# USB-C.net
KiCad netlist of a schematic drawn in Altium Designer
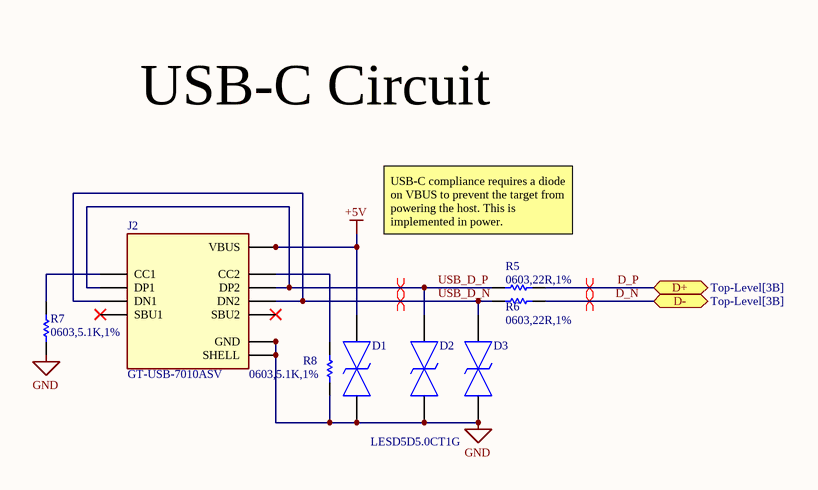
[diagram p0: USB-C.SchDoc]

(export (version "E")
  (design (tool "Eeschema 10.0.6"))
  (components
    (comp (ref "D1")
      (value "LESD5D5.0CT1G")
      (footprint "LESD5D50CT1G")
      (description "9.4A 18.6V 5.6V Bidirectional 5V SOD-523 ESD and Surge Protection (TVS/ESD) ROHS")
      (fields (field (name "LCSC PART NUMBER") "C383211"))
      (libsource (lib "LC-SchLib") (part "LESD5D5.0CT1G"))
    )
    (comp (ref "D2")
      (value "LESD5D5.0CT1G")
      (footprint "LESD5D50CT1G")
      (description "9.4A 18.6V 5.6V Bidirectional 5V SOD-523 ESD and Surge Protection (TVS/ESD) ROHS")
      (fields (field (name "LCSC PART NUMBER") "C383211"))
      (libsource (lib "LC-SchLib") (part "LESD5D5.0CT1G"))
    )
    (comp (ref "D3")
      (value "LESD5D5.0CT1G")
      (footprint "LESD5D50CT1G")
      (description "9.4A 18.6V 5.6V Bidirectional 5V SOD-523 ESD and Surge Protection (TVS/ESD) ROHS")
      (fields (field (name "LCSC PART NUMBER") "C383211"))
      (libsource (lib "LC-SchLib") (part "LESD5D5.0CT1G"))
    )
    (comp (ref "J2")
      (value "GT-USB-7010ASV")
      (footprint "USB-C-SMD_G-SWITCH_GT-USB-7010ASV")
      (description "USB 2.0 3A 1 Surface Mount, Right Angle 16P Female -40℃~+85℃ Type-C SMD USB Connectors ROHS")
      (fields (field (name "LCSC PART NUMBER") "C2988369"))
      (libsource (lib "LC-SchLib") (part "GT-USB-7010ASV"))
    )
    (comp (ref "R5")
      (value "0603,22R,1%")
      (footprint "RESC1608X55N")
      (description "100mW Thick Film Resistor 75V ±100ppm/℃ ±1% 22Ω 0603 Chip Resistor - Surface Mount ROHS")
      (fields
        (field (name "MANUFACTURER_PART_NUMBER") "RC0603FR-0722RL")
        (field (name "MOUSER PART NUMBER") "603-RC0603FR-0722RL")
      )
      (libsource (lib "LC-SchLib") (part "RC0603FR-0722RL"))
    )
    (comp (ref "R6")
      (value "0603,22R,1%")
      (footprint "RESC1608X55N")
      (description "100mW Thick Film Resistor 75V ±100ppm/℃ ±1% 22Ω 0603 Chip Resistor - Surface Mount ROHS")
      (fields
        (field (name "MANUFACTURER_PART_NUMBER") "RC0603FR-0722RL")
        (field (name "MOUSER PART NUMBER") "603-RC0603FR-0722RL")
      )
      (libsource (lib "LC-SchLib") (part "RC0603FR-0722RL"))
    )
    (comp (ref "R7")
      (value "0603,5.1K,1%")
      (footprint "RESC1608X55N")
      (description "100mW Thick Film Resistor 75V ±100ppm/℃ ±1% 5.1kΩ 0603 Chip Resistor - Surface Mount ROHS")
      (fields
        (field (name "MANUFACTURER_PART_NUMBER") "RC0603FR-0710KL")
        (field (name "MOUSER PART NUMBER") "603-RC0603FR-0710KL")
      )
      (libsource (lib "LC-SchLib") (part "RC0603FR-075K1L"))
    )
    (comp (ref "R8")
      (value "0603,5.1K,1%")
      (footprint "RESC1608X55N")
      (description "100mW Thick Film Resistor 75V ±100ppm/℃ ±1% 5.1kΩ 0603 Chip Resistor - Surface Mount ROHS")
      (fields
        (field (name "MANUFACTURER_PART_NUMBER") "RC0603FR-0710KL")
        (field (name "MOUSER PART NUMBER") "603-RC0603FR-0710KL")
      )
      (libsource (lib "LC-SchLib") (part "RC0603FR-075K1L"))
    )
  )
  (nets
    (net (code "1") (name "+5V") (class "Default")
      (node (ref "D1") (pin "2") (pinfunction "2_2") (pintype "passive"))
      (node (ref "J2") (pin "A4B9") (pinfunction "VBUS_A4B9") (pintype "passive"))
      (node (ref "J2") (pin "B4A9") (pinfunction "VBUS_B4A9") (pintype "passive"))
    )
    (net (code "2") (name "/D_N") (class "Default")
      (node (ref "R6") (pin "2") (pinfunction "2_2") (pintype "passive"))
    )
    (net (code "3") (name "/D_P") (class "Default")
      (node (ref "R5") (pin "2") (pinfunction "2_2") (pintype "passive"))
    )
    (net (code "4") (name "/USB_D_N") (class "Default")
      (node (ref "D3") (pin "2") (pinfunction "2_2") (pintype "passive"))
      (node (ref "J2") (pin "A7") (pinfunction "DN1_A7") (pintype "passive"))
      (node (ref "J2") (pin "B7") (pinfunction "DN2_B7") (pintype "passive"))
      (node (ref "R6") (pin "1") (pinfunction "1_1") (pintype "passive"))
    )
    (net (code "5") (name "/USB_D_P") (class "Default")
      (node (ref "D2") (pin "2") (pinfunction "2_2") (pintype "passive"))
      (node (ref "J2") (pin "A6") (pinfunction "DP1_A6") (pintype "passive"))
      (node (ref "J2") (pin "B6") (pinfunction "DP2_B6") (pintype "passive"))
      (node (ref "R5") (pin "1") (pinfunction "1_1") (pintype "passive"))
    )
    (net (code "6") (name "GND") (class "Default")
      (node (ref "D1") (pin "1") (pinfunction "1_1") (pintype "passive"))
      (node (ref "D2") (pin "1") (pinfunction "1_1") (pintype "passive"))
      (node (ref "D3") (pin "1") (pinfunction "1_1") (pintype "passive"))
      (node (ref "J2") (pin "1") (pinfunction "SHELL_1") (pintype "passive"))
      (node (ref "J2") (pin "2") (pinfunction "SHELL_2") (pintype "passive"))
      (node (ref "J2") (pin "3") (pinfunction "SHELL_3") (pintype "passive"))
      (node (ref "J2") (pin "4") (pinfunction "SHELL_4") (pintype "passive"))
      (node (ref "J2") (pin "A1B12") (pinfunction "GND_A1B12") (pintype "passive"))
      (node (ref "J2") (pin "B1A12") (pinfunction "GND_B1A12") (pintype "passive"))
      (node (ref "R7") (pin "1") (pinfunction "1_1") (pintype "passive"))
      (node (ref "R8") (pin "1") (pinfunction "1_1") (pintype "passive"))
    )
    (net (code "7") (name "Net-(J2-CC1)") (class "Default")
      (node (ref "J2") (pin "A5") (pinfunction "CC1_A5") (pintype "passive"))
      (node (ref "R7") (pin "2") (pinfunction "2_2") (pintype "passive"))
    )
    (net (code "8") (name "Net-(J2-CC2)") (class "Default")
      (node (ref "J2") (pin "B5") (pinfunction "CC2_B5") (pintype "passive"))
      (node (ref "R8") (pin "2") (pinfunction "2_2") (pintype "passive"))
    )
    (net (code "9") (name "unconnected-(J2-SBU1-PadA8)") (class "Default")
      (node (ref "J2") (pin "A8") (pinfunction "SBU1_A8") (pintype "passive+no_connect"))
    )
    (net (code "10") (name "unconnected-(J2-SBU2-PadB8)") (class "Default")
      (node (ref "J2") (pin "B8") (pinfunction "SBU2_B8") (pintype "passive+no_connect"))
    )
  )
)
